# POWER.net
KiCad netlist of a schematic drawn in Altium Designer
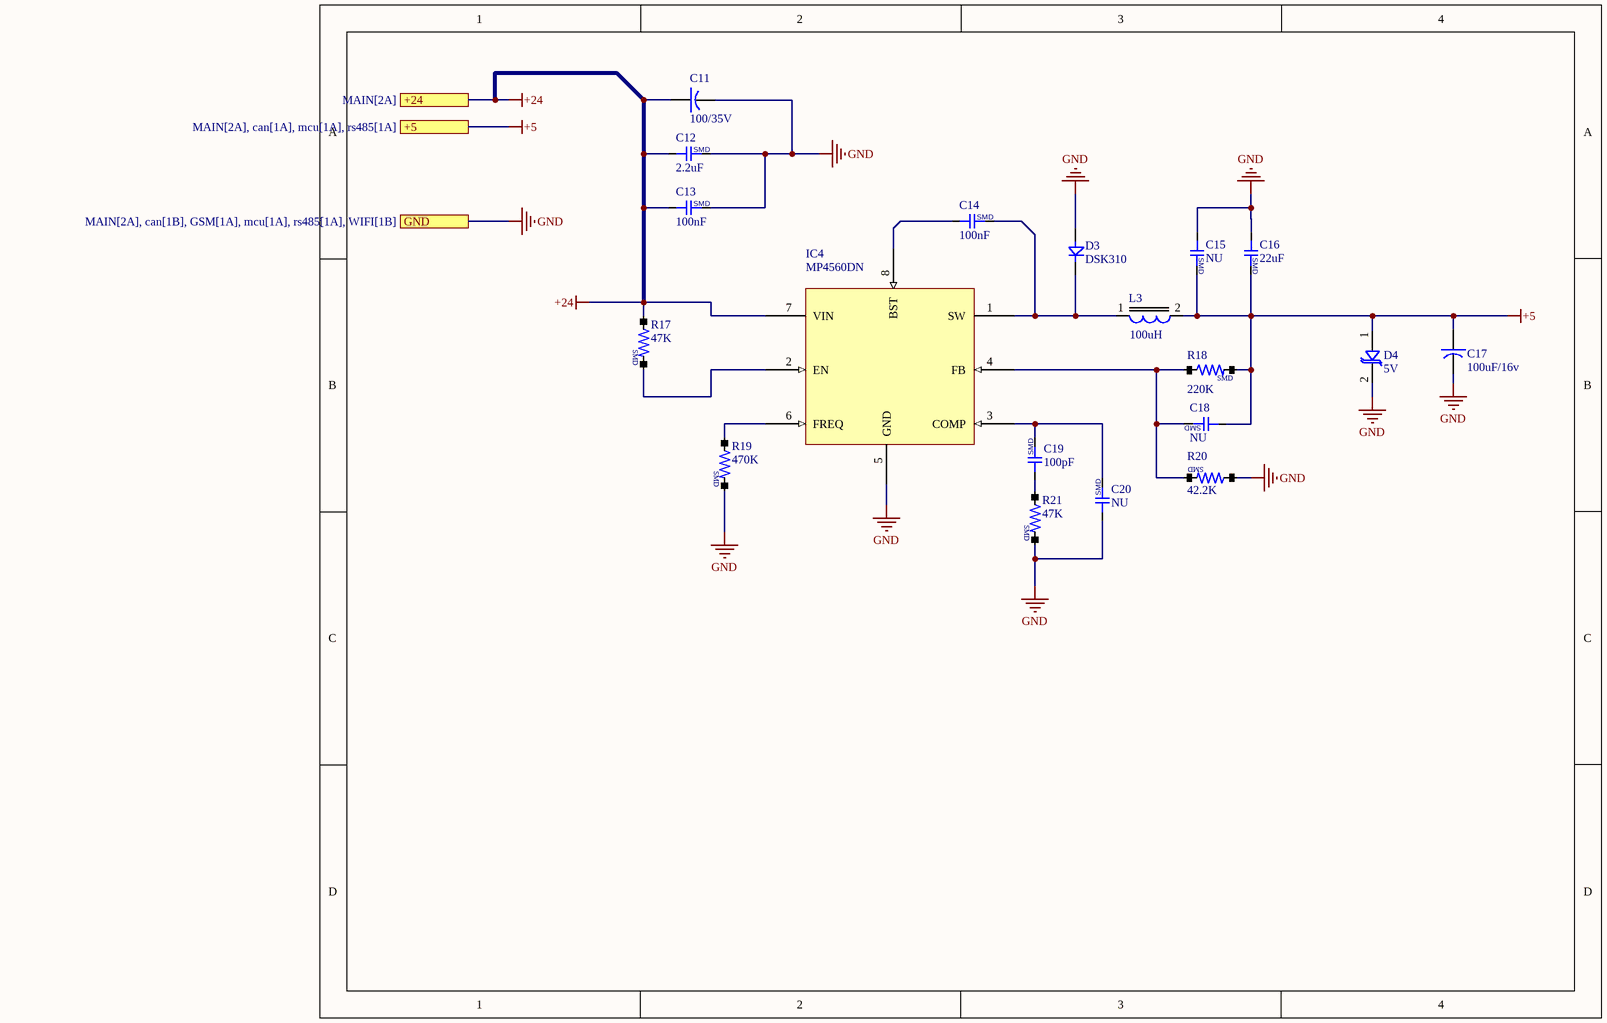
[diagram p0: POWER.SchDoc]

(export (version "E")
  (design (tool "Eeschema 10.0.6"))
  (components
    (comp (ref "C11")
      (value "100/35V")
      (footprint "cap/330u/16v")
      (libsource (lib "kave-eng-pro") (part "cap-electrolit"))
    )
    (comp (ref "C12")
      (value "2.2uF")
      (footprint "CAP-0805")
      (libsource (lib "kave-eng-pro") (part "cap_smd"))
    )
    (comp (ref "C13")
      (value "100nF")
      (footprint "CAP-0603")
      (libsource (lib "kave-eng-pro") (part "cap_smd"))
    )
    (comp (ref "C14")
      (value "100nF")
      (footprint "CAP-0603")
      (libsource (lib "kave-eng-pro") (part "cap_smd"))
    )
    (comp (ref "C15") (value "NU") (footprint "CAP-1206") (libsource (lib "kave-eng-pro") (part "cap_smd")))
    (comp (ref "C16") (value "22uF") (footprint "CAP-1206") (libsource (lib "kave-eng-pro") (part "cap_smd")))
    (comp (ref "C17")
      (value "100uF/16v")
      (footprint "cap/330u/16v")
      (libsource (lib "kave-eng-pro") (part "cap-electrolit"))
    )
    (comp (ref "C18") (value "NU") (footprint "CAP-0603") (libsource (lib "kave-eng-pro") (part "cap_smd")))
    (comp (ref "C19")
      (value "100pF")
      (footprint "CAP-0603")
      (libsource (lib "kave-eng-pro") (part "cap_smd"))
    )
    (comp (ref "C20") (value "NU") (footprint "CAP-0603") (libsource (lib "kave-eng-pro") (part "cap_smd")))
    (comp (ref "D3")
      (value "DSK310")
      (footprint "DIOD/1N4007/SMD")
      (libsource (lib "kave-eng-pro") (part "DIOD/RECTIFIERS"))
    )
    (comp (ref "D4") (value "5V") (footprint "TVS-5V-SMD") (libsource (lib "kave-eng-pro") (part "TVS-SMD")))
    (comp (ref "IC4")
      (value "MP4560DN")
      (footprint "SOP8_HIT")
      (libsource (lib "kave-eng-pro") (part "MP4560DN"))
    )
    (comp (ref "L3")
      (value "100uH")
      (footprint "inductor-9*12")
      (libsource (lib "kave-eng-pro") (part "inductor"))
    )
    (comp (ref "R17") (value "47K") (footprint "RES/0603") (libsource (lib "kave-eng-pro") (part "RES/SMD")))
    (comp (ref "R18") (value "220K") (footprint "RES/0603") (libsource (lib "") (part "RES/SMD_1")))
    (comp (ref "R19") (value "470K") (footprint "RES/0603") (libsource (lib "kave-eng-pro") (part "RES/SMD")))
    (comp (ref "R20") (value "42.2K") (footprint "RES/0603") (libsource (lib "") (part "RES/SMD_2")))
    (comp (ref "R21") (value "47K") (footprint "RES/0603") (libsource (lib "kave-eng-pro") (part "RES/SMD")))
  )
  (nets
    (net (code "1") (name "+5") (class "Default")
      (node (ref "C15") (pin "2") (pintype "passive"))
      (node (ref "C16") (pin "2") (pintype "passive"))
      (node (ref "C17") (pin "+") (pintype "passive"))
      (node (ref "C18") (pin "1") (pintype "passive"))
      (node (ref "D4") (pin "1") (pintype "passive"))
      (node (ref "L3") (pin "2") (pintype "passive"))
      (node (ref "R18") (pin "2") (pinfunction "2_2") (pintype "passive"))
    )
    (net (code "2") (name "+24") (class "Default")
      (node (ref "C11") (pin "+") (pintype "passive"))
      (node (ref "C12") (pin "1") (pintype "passive"))
      (node (ref "C13") (pin "1") (pintype "passive"))
      (node (ref "IC4") (pin "7") (pinfunction "VIN_7") (pintype "power_in"))
      (node (ref "R17") (pin "1") (pinfunction "1_1") (pintype "passive"))
    )
    (net (code "3") (name "GND") (class "Default")
      (node (ref "C11") (pin "-") (pintype "passive"))
      (node (ref "C12") (pin "2") (pintype "passive"))
      (node (ref "C13") (pin "2") (pintype "passive"))
      (node (ref "C15") (pin "1") (pintype "passive"))
      (node (ref "C16") (pin "1") (pintype "passive"))
      (node (ref "C17") (pin "-") (pintype "passive"))
      (node (ref "C20") (pin "1") (pintype "passive"))
      (node (ref "D3") (pin "A") (pintype "passive"))
      (node (ref "D4") (pin "2") (pintype "passive"))
      (node (ref "IC4") (pin "5") (pinfunction "GND_5") (pintype "power_in"))
      (node (ref "R19") (pin "2") (pinfunction "2_2") (pintype "passive"))
      (node (ref "R20") (pin "1") (pinfunction "1_1") (pintype "passive"))
      (node (ref "R21") (pin "2") (pinfunction "2_2") (pintype "passive"))
    )
    (net (code "4") (name "Net-(C19-Pad1)") (class "Default")
      (node (ref "C19") (pin "1") (pintype "passive"))
      (node (ref "R21") (pin "1") (pinfunction "1_1") (pintype "passive"))
    )
    (net (code "5") (name "Net-(IC4-BST)") (class "Default")
      (node (ref "C14") (pin "1") (pintype "passive"))
      (node (ref "IC4") (pin "8") (pinfunction "BST_8") (pintype "input"))
    )
    (net (code "6") (name "Net-(IC4-COMP)") (class "Default")
      (node (ref "C19") (pin "2") (pintype "passive"))
      (node (ref "C20") (pin "2") (pintype "passive"))
      (node (ref "IC4") (pin "3") (pinfunction "COMP_3") (pintype "input"))
    )
    (net (code "7") (name "Net-(IC4-EN)") (class "Default")
      (node (ref "IC4") (pin "2") (pinfunction "EN_2") (pintype "input"))
      (node (ref "R17") (pin "2") (pinfunction "2_2") (pintype "passive"))
    )
    (net (code "8") (name "Net-(IC4-FB)") (class "Default")
      (node (ref "C18") (pin "2") (pintype "passive"))
      (node (ref "IC4") (pin "4") (pinfunction "FB_4") (pintype "input"))
      (node (ref "R18") (pin "1") (pinfunction "1_1") (pintype "passive"))
      (node (ref "R20") (pin "2") (pinfunction "2_2") (pintype "passive"))
    )
    (net (code "9") (name "Net-(IC4-FREQ)") (class "Default")
      (node (ref "IC4") (pin "6") (pinfunction "FREQ_6") (pintype "input"))
      (node (ref "R19") (pin "1") (pinfunction "1_1") (pintype "passive"))
    )
    (net (code "10") (name "Net-(IC4-SW)") (class "Default")
      (node (ref "C14") (pin "2") (pintype "passive"))
      (node (ref "D3") (pin "K") (pintype "passive"))
      (node (ref "IC4") (pin "1") (pinfunction "SW_1") (pintype "power_in"))
      (node (ref "L3") (pin "1") (pintype "passive"))
    )
  )
)
